# SN74ABT273DBR_Breakout.net
KiCad netlist of a schematic drawn in EAGLE
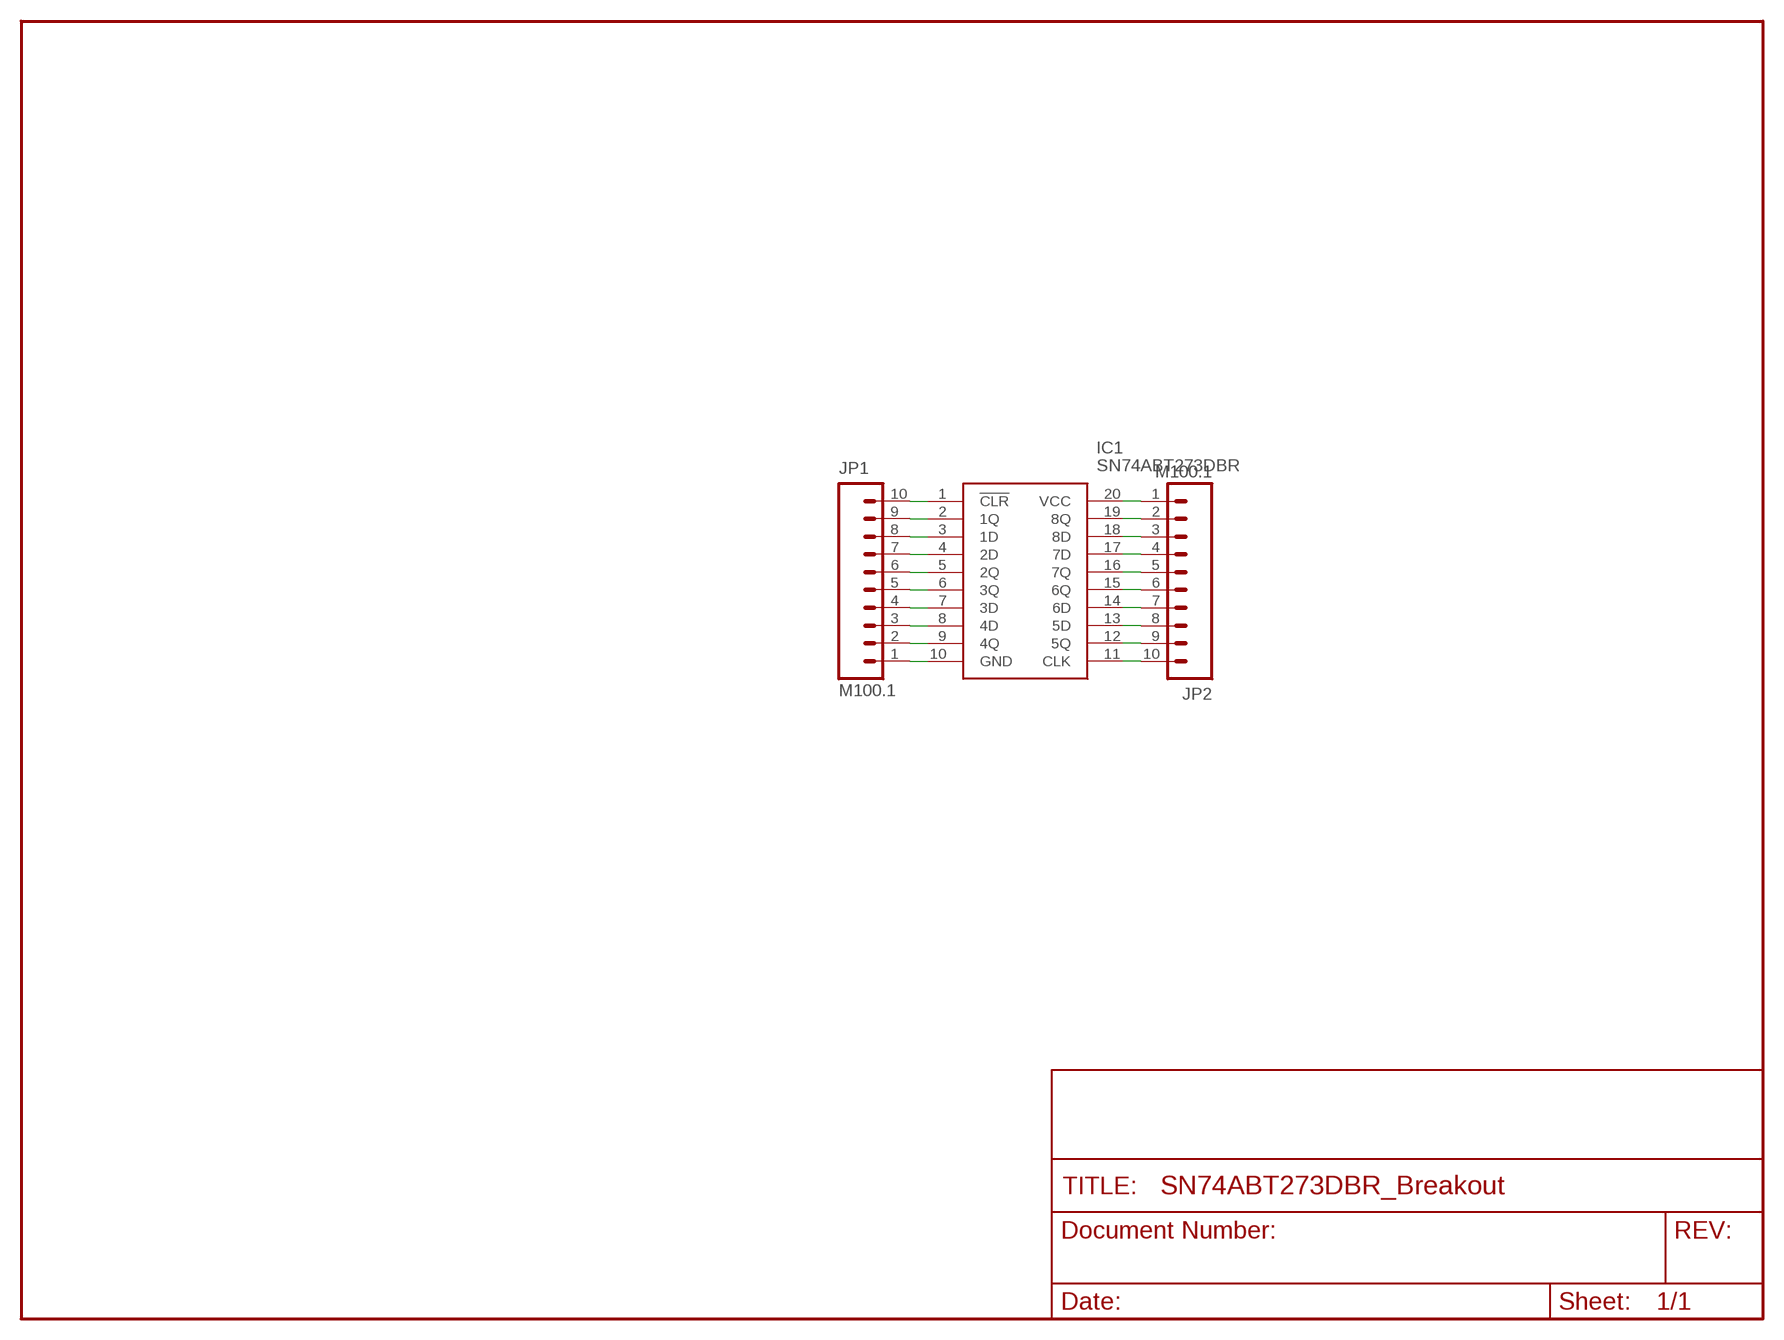
[diagram p0: schematic, sheet 1]

(export (version "E")
  (design (tool "Eeschema 10.0.6"))
  (components
    (comp (ref "IC1")
      (value "SN74ABT273DBR")
      (footprint "eagle-import:SOP65P780X200-20N")
      (fields (field (name "MOUSER_PART_NUMBER") "595-SN74ABT273DBR"))
      (libsource (lib "eagle-import") (part "SN74ABT273DBR"))
    )
    (comp (ref "JP1")
      (value "M100.1")
      (footprint "eagle-import:1X10")
      (libsource (lib "eagle-import") (part "M100.1"))
    )
    (comp (ref "JP2")
      (value "M100.1")
      (footprint "eagle-import:1X10")
      (libsource (lib "eagle-import") (part "M100.1"))
    )
  )
  (nets
    (net (code "1") (name "Net-(IC1-1D)") (class "Default")
      (node (ref "IC1") (pin "3") (pinfunction "1D_3") (pintype "bidirectional"))
      (node (ref "JP1") (pin "8") (pinfunction "8_8") (pintype "passive"))
    )
    (net (code "2") (name "Net-(IC1-1Q)") (class "Default")
      (node (ref "IC1") (pin "2") (pinfunction "1Q_2") (pintype "bidirectional"))
      (node (ref "JP1") (pin "9") (pinfunction "9_9") (pintype "passive"))
    )
    (net (code "3") (name "Net-(IC1-2D)") (class "Default")
      (node (ref "IC1") (pin "4") (pinfunction "2D_4") (pintype "bidirectional"))
      (node (ref "JP1") (pin "7") (pinfunction "7_7") (pintype "passive"))
    )
    (net (code "4") (name "Net-(IC1-2Q)") (class "Default")
      (node (ref "IC1") (pin "5") (pinfunction "2Q_5") (pintype "bidirectional"))
      (node (ref "JP1") (pin "6") (pinfunction "6_6") (pintype "passive"))
    )
    (net (code "5") (name "Net-(IC1-3D)") (class "Default")
      (node (ref "IC1") (pin "7") (pinfunction "3D_7") (pintype "bidirectional"))
      (node (ref "JP1") (pin "4") (pinfunction "4_4") (pintype "passive"))
    )
    (net (code "6") (name "Net-(IC1-3Q)") (class "Default")
      (node (ref "IC1") (pin "6") (pinfunction "3Q_6") (pintype "bidirectional"))
      (node (ref "JP1") (pin "5") (pinfunction "5_5") (pintype "passive"))
    )
    (net (code "7") (name "Net-(IC1-4D)") (class "Default")
      (node (ref "IC1") (pin "8") (pinfunction "4D_8") (pintype "bidirectional"))
      (node (ref "JP1") (pin "3") (pinfunction "3_3") (pintype "passive"))
    )
    (net (code "8") (name "Net-(IC1-4Q)") (class "Default")
      (node (ref "IC1") (pin "9") (pinfunction "4Q_9") (pintype "bidirectional"))
      (node (ref "JP1") (pin "2") (pinfunction "2_2") (pintype "passive"))
    )
    (net (code "9") (name "Net-(IC1-5D)") (class "Default")
      (node (ref "IC1") (pin "13") (pinfunction "5D_13") (pintype "bidirectional"))
      (node (ref "JP2") (pin "8") (pinfunction "8_8") (pintype "passive"))
    )
    (net (code "10") (name "Net-(IC1-5Q)") (class "Default")
      (node (ref "IC1") (pin "12") (pinfunction "5Q_12") (pintype "bidirectional"))
      (node (ref "JP2") (pin "9") (pinfunction "9_9") (pintype "passive"))
    )
    (net (code "11") (name "Net-(IC1-6D)") (class "Default")
      (node (ref "IC1") (pin "14") (pinfunction "6D_14") (pintype "bidirectional"))
      (node (ref "JP2") (pin "7") (pinfunction "7_7") (pintype "passive"))
    )
    (net (code "12") (name "Net-(IC1-6Q)") (class "Default")
      (node (ref "IC1") (pin "15") (pinfunction "6Q_15") (pintype "bidirectional"))
      (node (ref "JP2") (pin "6") (pinfunction "6_6") (pintype "passive"))
    )
    (net (code "13") (name "Net-(IC1-7D)") (class "Default")
      (node (ref "IC1") (pin "17") (pinfunction "7D_17") (pintype "bidirectional"))
      (node (ref "JP2") (pin "4") (pinfunction "4_4") (pintype "passive"))
    )
    (net (code "14") (name "Net-(IC1-7Q)") (class "Default")
      (node (ref "IC1") (pin "16") (pinfunction "7Q_16") (pintype "bidirectional"))
      (node (ref "JP2") (pin "5") (pinfunction "5_5") (pintype "passive"))
    )
    (net (code "15") (name "Net-(IC1-8D)") (class "Default")
      (node (ref "IC1") (pin "18") (pinfunction "8D_18") (pintype "bidirectional"))
      (node (ref "JP2") (pin "3") (pinfunction "3_3") (pintype "passive"))
    )
    (net (code "16") (name "Net-(IC1-8Q)") (class "Default")
      (node (ref "IC1") (pin "19") (pinfunction "8Q_19") (pintype "bidirectional"))
      (node (ref "JP2") (pin "2") (pinfunction "2_2") (pintype "passive"))
    )
    (net (code "17") (name "Net-(IC1-CLK)") (class "Default")
      (node (ref "IC1") (pin "11") (pinfunction "CLK_11") (pintype "bidirectional"))
      (node (ref "JP2") (pin "10") (pinfunction "10_10") (pintype "passive"))
    )
    (net (code "18") (name "Net-(IC1-GND)") (class "Default")
      (node (ref "IC1") (pin "10") (pinfunction "GND_10") (pintype "bidirectional"))
      (node (ref "JP1") (pin "1") (pinfunction "1_1") (pintype "passive"))
    )
    (net (code "19") (name "Net-(IC1-VCC)") (class "Default")
      (node (ref "IC1") (pin "20") (pinfunction "VCC_20") (pintype "bidirectional"))
      (node (ref "JP2") (pin "1") (pinfunction "1_1") (pintype "passive"))
    )
    (net (code "20") (name "Net-(IC1-~{CLR})") (class "Default")
      (node (ref "IC1") (pin "1") (pinfunction "~{CLR}_1") (pintype "bidirectional"))
      (node (ref "JP1") (pin "10") (pinfunction "10_10") (pintype "passive"))
    )
  )
)
